# SCH_stm32f103c8t6_test1_2023-07-15.net
KiCad netlist of a schematic drawn in EasyEDA
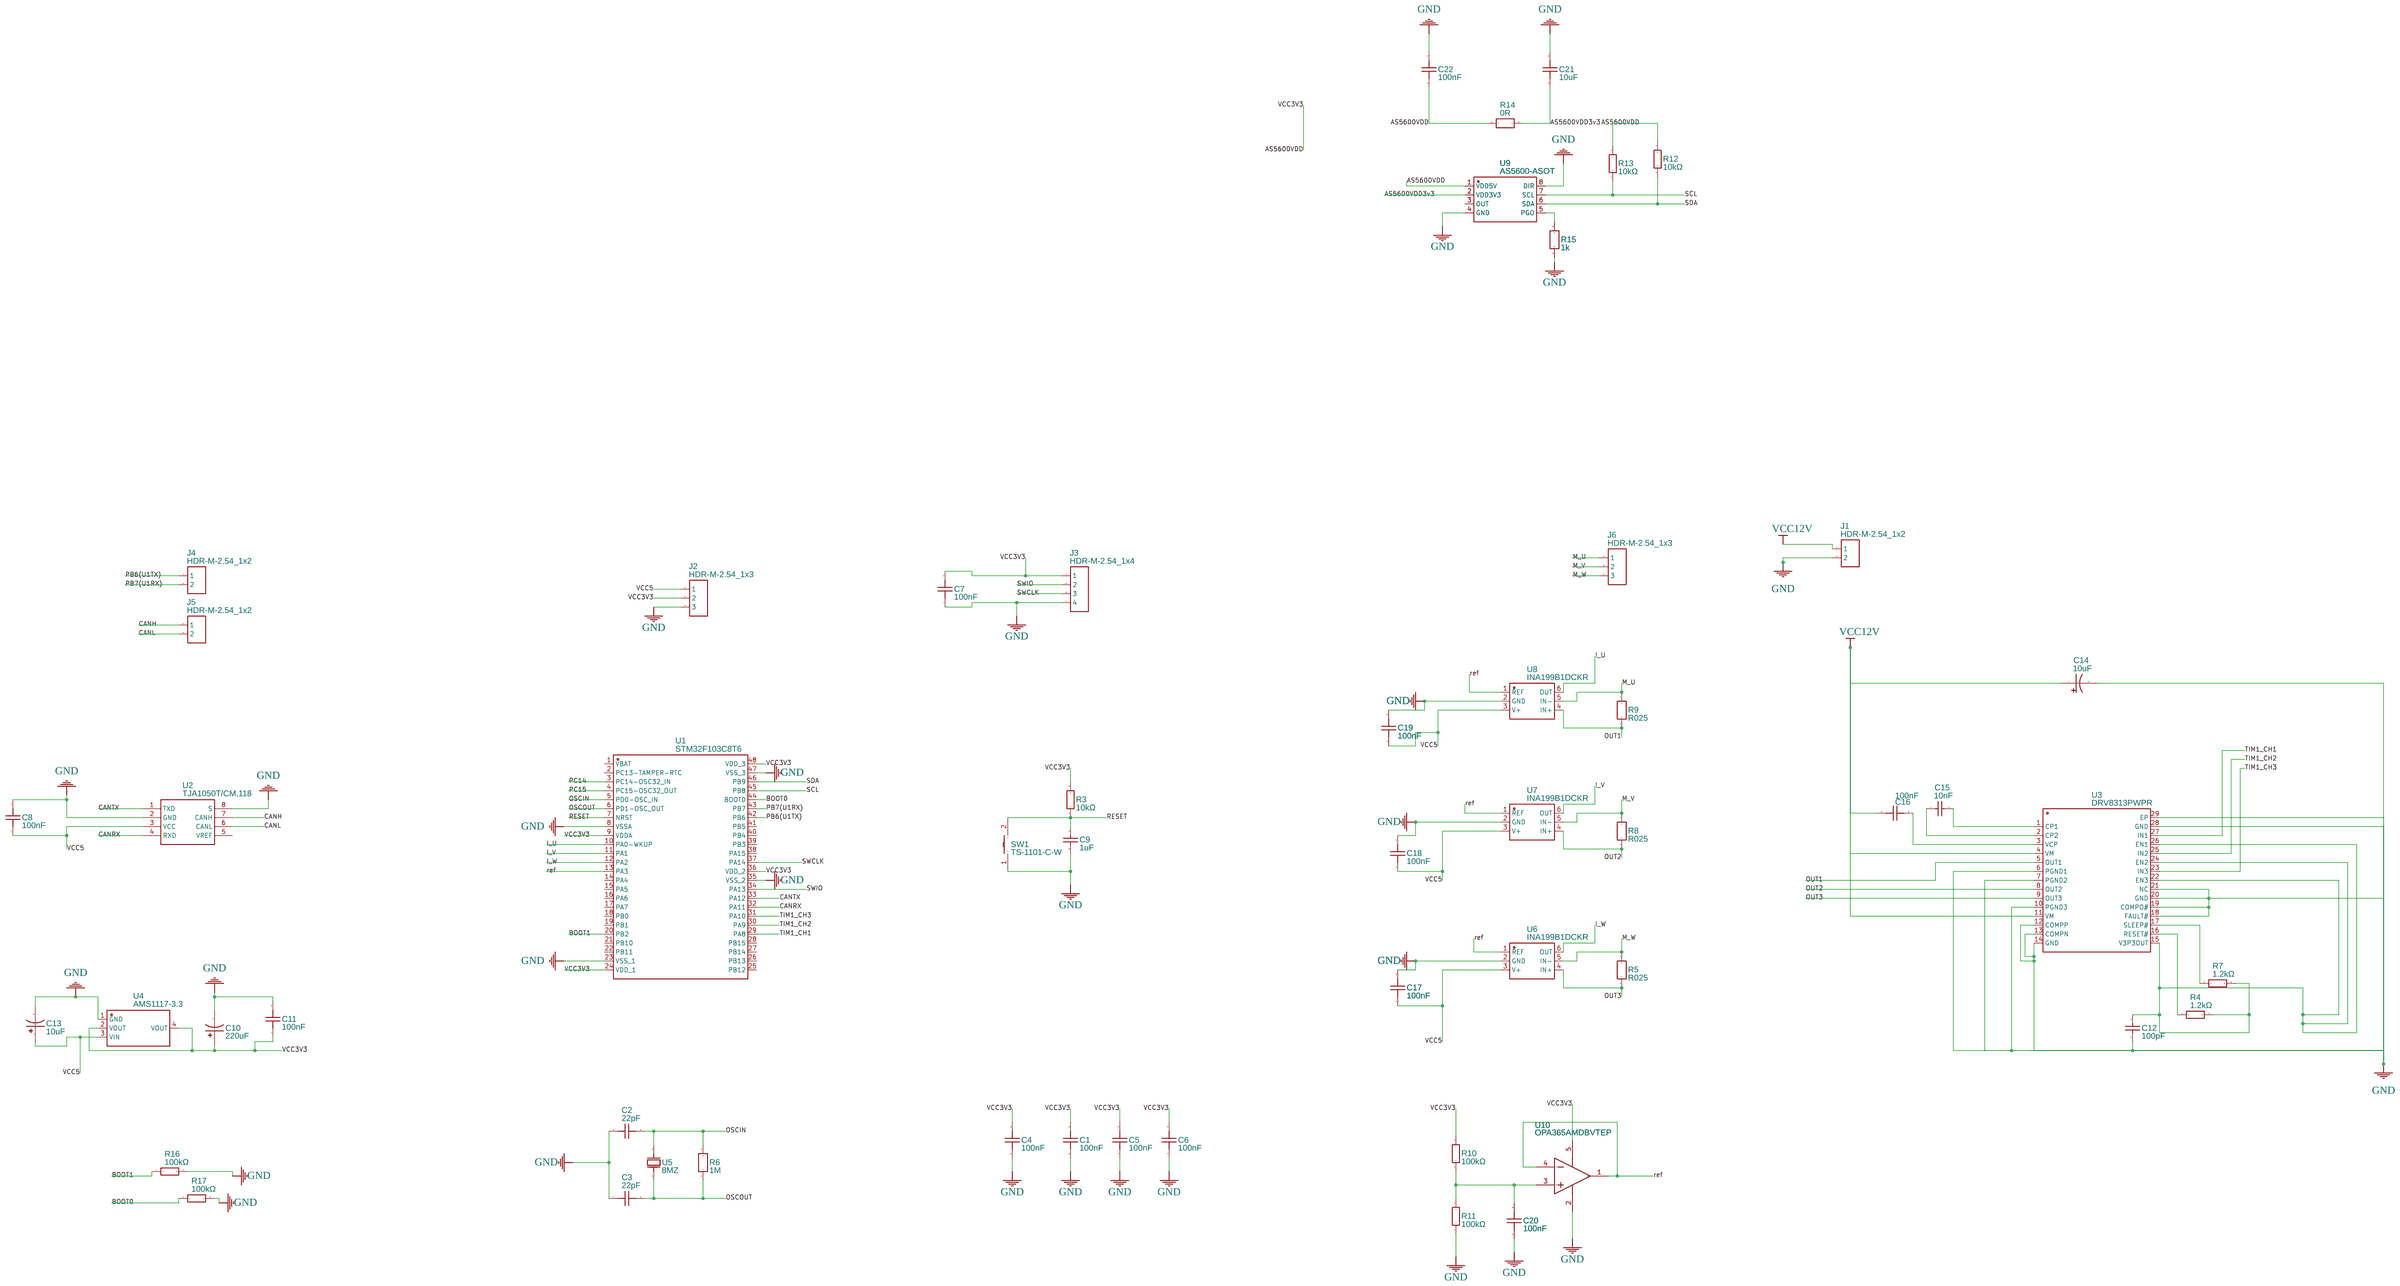
[diagram p0: schematic sheet]

(export (version "E")
  (design (tool "Eeschema 10.0.6"))
  (components
    (comp (ref "C1") (value "100nF") (libsource (lib "") (part "C_0603_US_1")))
    (comp (ref "C2") (value "22pF") (libsource (lib "") (part "C_0603_US")))
    (comp (ref "C3") (value "22pF") (libsource (lib "") (part "C_0603_US")))
    (comp (ref "C4") (value "100nF") (libsource (lib "") (part "C_0603_US_1")))
    (comp (ref "C5") (value "100nF") (libsource (lib "") (part "C_0603_US_1")))
    (comp (ref "C6") (value "100nF") (libsource (lib "") (part "C_0603_US_1")))
    (comp (ref "C7") (value "100nF") (libsource (lib "") (part "C_0603_US_1")))
    (comp (ref "C8") (value "100nF") (libsource (lib "") (part "C_0603_US_1")))
    (comp (ref "C9")
      (value "1uF")
      (fields
        (field (name "BOM_Manufacturer Part") "CGA3E1X7R1E105KT0Y0E")
        (field (name "BOM_Supplier Part") "C76708")
      )
      (libsource (lib "") (part "CGA3E1X7R1E105KT0Y0E"))
    )
    (comp (ref "C10") (value "220uF") (libsource (lib "") (part "C_Tan_SMD_C_US")))
    (comp (ref "C11") (value "100nF") (libsource (lib "") (part "C_0603_US_1")))
    (comp (ref "C12")
      (value "100pF")
      (fields
        (field (name "BOM_Manufacturer Part") "CGA3E2C0G2A101JT0Y0N")
        (field (name "BOM_Supplier Part") "C342908")
      )
      (libsource (lib "") (part "CGA3E2C0G2A101JT0Y0N"))
    )
    (comp (ref "C13") (value "10uF") (libsource (lib "") (part "C_Tan_SMD_A_US")))
    (comp (ref "C14")
      (value "10uF")
      (fields
        (field (name "BOM_Manufacturer Part") "NXA50VB10M5*11_LO")
        (field (name "BOM_Supplier Part") "C346966")
      )
      (libsource (lib "") (part "NXA50VB10M5*11_LO"))
    )
    (comp (ref "C15")
      (value "10nF")
      (fields
        (field (name "BOM_Manufacturer Part") "CGA3E2C0G1H103JT0Y0N")
        (field (name "BOM_Supplier Part") "C76710")
      )
      (libsource (lib "") (part "CGA3E2C0G1H103JT0Y0N"))
    )
    (comp (ref "C16")
      (value "100nF")
      (fields
        (field (name "BOM_Manufacturer Part") "0603B104K500")
        (field (name "BOM_Supplier Part") "C90807")
      )
      (libsource (lib "") (part "0603B104K500"))
    )
    (comp (ref "C17")
      (value "100nF")
      (fields
        (field (name "BOM_Manufacturer Part") "0603B104K500")
        (field (name "BOM_Supplier Part") "C90807")
      )
      (libsource (lib "") (part "0603B104K500_1"))
    )
    (comp (ref "C18")
      (value "100nF")
      (fields
        (field (name "BOM_Manufacturer Part") "0603B104K500")
        (field (name "BOM_Supplier Part") "C90807")
      )
      (libsource (lib "") (part "0603B104K500_1"))
    )
    (comp (ref "C19")
      (value "100nF")
      (fields
        (field (name "BOM_Manufacturer Part") "0603B104K500")
        (field (name "BOM_Supplier Part") "C90807")
      )
      (libsource (lib "") (part "0603B104K500_1"))
    )
    (comp (ref "C20") (value "100nF") (libsource (lib "") (part "C_0603_US_1")))
    (comp (ref "C21") (value "10uF") (libsource (lib "") (part "C_0603_US_1")))
    (comp (ref "C22") (value "100nF") (libsource (lib "") (part "C_0603_US_1")))
    (comp (ref "J1")
      (value "HDR-M-2.54_1x2")
      (fields (field (name "BOM_Supplier Part") "C124375"))
      (libsource (lib "") (part "HDR-M-2.54_1x2"))
    )
    (comp (ref "J2")
      (value "HDR-M-2.54_1x3")
      (fields (field (name "BOM_Supplier Part") "C180248"))
      (libsource (lib "") (part "HDR-M-2.54_1x3"))
    )
    (comp (ref "J3")
      (value "HDR-M-2.54_1x4")
      (fields (field (name "BOM_Supplier Part") "C124378"))
      (libsource (lib "") (part "HDR-M-2.54_1x4"))
    )
    (comp (ref "J4")
      (value "HDR-M-2.54_1x2")
      (fields (field (name "BOM_Supplier Part") "C124375"))
      (libsource (lib "") (part "HDR-M-2.54_1x2"))
    )
    (comp (ref "J5")
      (value "HDR-M-2.54_1x2")
      (fields (field (name "BOM_Supplier Part") "C124375"))
      (libsource (lib "") (part "HDR-M-2.54_1x2"))
    )
    (comp (ref "J6")
      (value "HDR-M-2.54_1x3")
      (fields (field (name "BOM_Supplier Part") "C180248"))
      (libsource (lib "") (part "HDR-M-2.54_1x3"))
    )
    (comp (ref "R3")
      (value "10kΩ")
      (fields
        (field (name "BOM_Manufacturer Part") "0603WAF1002T5E")
        (field (name "BOM_Supplier Part") "C25804")
      )
      (libsource (lib "") (part "0603WAF1002T5E"))
    )
    (comp (ref "R4")
      (value "1.2kΩ")
      (fields
        (field (name "BOM_Manufacturer Part") "RMC04021.2K1%N")
        (field (name "BOM_Supplier Part") "C325417")
      )
      (libsource (lib "") (part "RMC04021.2K1%N"))
    )
    (comp (ref "R5") (value "R025") (libsource (lib "") (part "R_2512_EU")))
    (comp (ref "R6") (value "1M") (libsource (lib "") (part "R_0603_EU")))
    (comp (ref "R7")
      (value "1.2kΩ")
      (fields
        (field (name "BOM_Manufacturer Part") "RMC04021.2K1%N")
        (field (name "BOM_Supplier Part") "C325417")
      )
      (libsource (lib "") (part "RMC04021.2K1%N"))
    )
    (comp (ref "R8") (value "R025") (libsource (lib "") (part "R_2512_EU")))
    (comp (ref "R9") (value "R025") (libsource (lib "") (part "R_2512_EU")))
    (comp (ref "R10")
      (value "100kΩ")
      (fields
        (field (name "BOM_Manufacturer Part") "AR03DTDX1003")
        (field (name "BOM_Supplier Part") "C319966")
      )
      (libsource (lib "") (part "AR03DTDX1003_1"))
    )
    (comp (ref "R11")
      (value "100kΩ")
      (fields
        (field (name "BOM_Manufacturer Part") "AR03DTDX1003")
        (field (name "BOM_Supplier Part") "C319966")
      )
      (libsource (lib "") (part "AR03DTDX1003_1"))
    )
    (comp (ref "R12")
      (value "10kΩ")
      (fields
        (field (name "BOM_Manufacturer Part") "0603WAF1002T5E")
        (field (name "BOM_Supplier Part") "C25804")
      )
      (libsource (lib "") (part "0603WAF1002T5E"))
    )
    (comp (ref "R13")
      (value "10kΩ")
      (fields
        (field (name "BOM_Manufacturer Part") "0603WAF1002T5E")
        (field (name "BOM_Supplier Part") "C25804")
      )
      (libsource (lib "") (part "0603WAF1002T5E"))
    )
    (comp (ref "R14") (value "0R") (libsource (lib "") (part "R_0603_EU_1")))
    (comp (ref "R15") (value "1k") (libsource (lib "") (part "R_0603_EU")))
    (comp (ref "R16")
      (value "100kΩ")
      (fields
        (field (name "BOM_Manufacturer Part") "AR03DTDX1003")
        (field (name "BOM_Supplier Part") "C319966")
      )
      (libsource (lib "") (part "AR03DTDX1003"))
    )
    (comp (ref "R17")
      (value "100kΩ")
      (fields
        (field (name "BOM_Manufacturer Part") "AR03DTDX1003")
        (field (name "BOM_Supplier Part") "C319966")
      )
      (libsource (lib "") (part "AR03DTDX1003"))
    )
    (comp (ref "SW1")
      (value "TS-1101-C-W")
      (fields (field (name "BOM_Supplier Part") "C318938"))
      (libsource (lib "") (part "TS-1101-C-W"))
    )
    (comp (ref "U1")
      (value "STM32F103C8T6")
      (fields (field (name "BOM_Supplier Part") "C8734"))
      (libsource (lib "") (part "STM32F103C8T6"))
    )
    (comp (ref "U2")
      (value "TJA1050T/CM,118")
      (fields (field (name "BOM_Supplier Part") "C6952"))
      (libsource (lib "") (part "TJA1050T/CM,118"))
    )
    (comp (ref "U3")
      (value "DRV8313PWPR")
      (fields (field (name "BOM_Supplier Part") "C92482"))
      (libsource (lib "") (part "DRV8313PWPR"))
    )
    (comp (ref "U4")
      (value "AMS1117-3.3")
      (fields (field (name "BOM_Supplier Part") "C6186"))
      (libsource (lib "") (part "AMS1117-3.3"))
    )
    (comp (ref "U5")
      (value "8MZ")
      (fields
        (field (name "BOM_Manufacturer Part") "S1C39321XWJAC")
        (field (name "BOM_Supplier Part") "C2764489")
      )
      (libsource (lib "") (part "S1C39321XWJAC"))
    )
    (comp (ref "U6")
      (value "INA199B1DCKR")
      (fields (field (name "BOM_Supplier Part") "C398920"))
      (libsource (lib "") (part "INA199B1DCKR"))
    )
    (comp (ref "U7")
      (value "INA199B1DCKR")
      (fields (field (name "BOM_Supplier Part") "C398920"))
      (libsource (lib "") (part "INA199B1DCKR"))
    )
    (comp (ref "U8")
      (value "INA199B1DCKR")
      (fields (field (name "BOM_Supplier Part") "C398920"))
      (libsource (lib "") (part "INA199B1DCKR"))
    )
    (comp (ref "U9")
      (value "AS5600-ASOT")
      (fields (field (name "BOM_Supplier Part") "C499458"))
      (libsource (lib "") (part "AS5600-ASOT"))
    )
    (comp (ref "U10")
      (value "OPA365AMDBVTEP")
      (fields (field (name "BOM_Supplier Part") "C2862994"))
      (libsource (lib "") (part "OPA365AMDBVTEP"))
    )
  )
  (nets
    (net (code "1") (name "/AS5600VDD") (class "Default")
      (node (ref "C1") (pin "2") (pinfunction "2_2") (pintype "unspecified"))
      (node (ref "C10") (pin "1") (pinfunction "1_1") (pintype "unspecified"))
      (node (ref "C11") (pin "1") (pinfunction "1_1") (pintype "unspecified"))
      (node (ref "C22") (pin "1") (pinfunction "1_1") (pintype "unspecified"))
      (node (ref "C4") (pin "2") (pinfunction "2_2") (pintype "unspecified"))
      (node (ref "C5") (pin "2") (pinfunction "2_2") (pintype "unspecified"))
      (node (ref "C6") (pin "2") (pinfunction "2_2") (pintype "unspecified"))
      (node (ref "C7") (pin "2") (pinfunction "2_2") (pintype "unspecified"))
      (node (ref "J2") (pin "2") (pinfunction "2_2") (pintype "input"))
      (node (ref "J3") (pin "1") (pinfunction "1_1") (pintype "unspecified"))
      (node (ref "R10") (pin "2") (pinfunction "2_2") (pintype "unspecified"))
      (node (ref "R12") (pin "2") (pinfunction "2_2") (pintype "input"))
      (node (ref "R13") (pin "2") (pinfunction "2_2") (pintype "input"))
      (node (ref "R14") (pin "1") (pinfunction "1_1") (pintype "unspecified"))
      (node (ref "R3") (pin "2") (pinfunction "2_2") (pintype "input"))
      (node (ref "U1") (pin "24") (pinfunction "VDD_1_24") (pintype "unspecified"))
      (node (ref "U1") (pin "36") (pinfunction "VDD_2_36") (pintype "unspecified"))
      (node (ref "U1") (pin "48") (pinfunction "VDD_3_48") (pintype "unspecified"))
      (node (ref "U1") (pin "9") (pinfunction "VDDA_9") (pintype "unspecified"))
      (node (ref "U10") (pin "5") (pinfunction "V+_5") (pintype "passive"))
      (node (ref "U4") (pin "2") (pinfunction "VOUT_2") (pintype "unspecified"))
      (node (ref "U4") (pin "4") (pinfunction "VOUT_4") (pintype "unspecified"))
      (node (ref "U9") (pin "1") (pinfunction "VDD5V_1") (pintype "unspecified"))
    )
    (net (code "2") (name "/AS5600VDD3v3") (class "Default")
      (node (ref "C21") (pin "1") (pinfunction "1_1") (pintype "unspecified"))
      (node (ref "R14") (pin "2") (pinfunction "2_2") (pintype "unspecified"))
      (node (ref "U9") (pin "2") (pinfunction "VDD3V3_2") (pintype "unspecified"))
    )
    (net (code "3") (name "/BOOT0") (class "Default")
      (node (ref "R17") (pin "1") (pinfunction "1_1") (pintype "unspecified"))
      (node (ref "U1") (pin "44") (pinfunction "BOOT0_44") (pintype "unspecified"))
    )
    (net (code "4") (name "/BOOT1") (class "Default")
      (node (ref "R16") (pin "1") (pinfunction "1_1") (pintype "unspecified"))
      (node (ref "U1") (pin "20") (pinfunction "PB2_20") (pintype "unspecified"))
    )
    (net (code "5") (name "/CANH") (class "Default")
      (node (ref "J5") (pin "1") (pinfunction "1_1") (pintype "unspecified"))
      (node (ref "U2") (pin "7") (pinfunction "CANH_7") (pintype "unspecified"))
    )
    (net (code "6") (name "/CANL") (class "Default")
      (node (ref "J5") (pin "2") (pinfunction "2_2") (pintype "unspecified"))
      (node (ref "U2") (pin "6") (pinfunction "CANL_6") (pintype "unspecified"))
    )
    (net (code "7") (name "/CANRX") (class "Default")
      (node (ref "U1") (pin "32") (pinfunction "PA11_32") (pintype "unspecified"))
      (node (ref "U2") (pin "4") (pinfunction "RXD_4") (pintype "unspecified"))
    )
    (net (code "8") (name "/CANTX") (class "Default")
      (node (ref "U1") (pin "33") (pinfunction "PA12_33") (pintype "unspecified"))
      (node (ref "U2") (pin "1") (pinfunction "TXD_1") (pintype "unspecified"))
    )
    (net (code "9") (name "/I_U") (class "Default")
      (node (ref "U1") (pin "10") (pinfunction "PA0-WKUP_10") (pintype "unspecified"))
      (node (ref "U8") (pin "6") (pinfunction "OUT_6") (pintype "unspecified"))
    )
    (net (code "10") (name "/I_V") (class "Default")
      (node (ref "U1") (pin "11") (pinfunction "PA1_11") (pintype "unspecified"))
      (node (ref "U7") (pin "6") (pinfunction "OUT_6") (pintype "unspecified"))
    )
    (net (code "11") (name "/I_W") (class "Default")
      (node (ref "U1") (pin "12") (pinfunction "PA2_12") (pintype "unspecified"))
      (node (ref "U6") (pin "6") (pinfunction "OUT_6") (pintype "unspecified"))
    )
    (net (code "12") (name "/M_U") (class "Default")
      (node (ref "J6") (pin "1") (pinfunction "1_1") (pintype "input"))
      (node (ref "R9") (pin "1") (pinfunction "1_1") (pintype "unspecified"))
      (node (ref "U8") (pin "5") (pinfunction "IN-_5") (pintype "unspecified"))
    )
    (net (code "13") (name "/M_V") (class "Default")
      (node (ref "J6") (pin "2") (pinfunction "2_2") (pintype "input"))
      (node (ref "R8") (pin "1") (pinfunction "1_1") (pintype "unspecified"))
      (node (ref "U7") (pin "5") (pinfunction "IN-_5") (pintype "unspecified"))
    )
    (net (code "14") (name "/M_W") (class "Default")
      (node (ref "J6") (pin "3") (pinfunction "3_3") (pintype "input"))
      (node (ref "R5") (pin "1") (pinfunction "1_1") (pintype "unspecified"))
      (node (ref "U6") (pin "5") (pinfunction "IN-_5") (pintype "unspecified"))
    )
    (net (code "15") (name "/OSCIN") (class "Default")
      (node (ref "C2") (pin "2") (pinfunction "2_2") (pintype "unspecified"))
      (node (ref "R6") (pin "2") (pinfunction "2_2") (pintype "unspecified"))
      (node (ref "U1") (pin "5") (pinfunction "PD0-OSC_IN_5") (pintype "unspecified"))
      (node (ref "U5") (pin "2") (pinfunction "OSC2_2") (pintype "input"))
    )
    (net (code "16") (name "/OSCOUT") (class "Default")
      (node (ref "C3") (pin "2") (pinfunction "2_2") (pintype "unspecified"))
      (node (ref "R6") (pin "1") (pinfunction "1_1") (pintype "unspecified"))
      (node (ref "U1") (pin "6") (pinfunction "PD1-OSC_OUT_6") (pintype "unspecified"))
      (node (ref "U5") (pin "1") (pinfunction "OSC1_1") (pintype "input"))
    )
    (net (code "17") (name "/OUT1") (class "Default")
      (node (ref "R9") (pin "2") (pinfunction "2_2") (pintype "unspecified"))
      (node (ref "U3") (pin "5") (pinfunction "OUT1_5") (pintype "unspecified"))
      (node (ref "U8") (pin "4") (pinfunction "IN+_4") (pintype "unspecified"))
    )
    (net (code "18") (name "/OUT2") (class "Default")
      (node (ref "R8") (pin "2") (pinfunction "2_2") (pintype "unspecified"))
      (node (ref "U3") (pin "8") (pinfunction "OUT2_8") (pintype "unspecified"))
      (node (ref "U7") (pin "4") (pinfunction "IN+_4") (pintype "unspecified"))
    )
    (net (code "19") (name "/OUT3") (class "Default")
      (node (ref "R5") (pin "2") (pinfunction "2_2") (pintype "unspecified"))
      (node (ref "U3") (pin "9") (pinfunction "OUT3_9") (pintype "unspecified"))
      (node (ref "U6") (pin "4") (pinfunction "IN+_4") (pintype "unspecified"))
    )
    (net (code "20") (name "/PB6(U1TX)") (class "Default")
      (node (ref "J4") (pin "1") (pinfunction "1_1") (pintype "unspecified"))
      (node (ref "U1") (pin "42") (pinfunction "PB6_42") (pintype "unspecified"))
    )
    (net (code "21") (name "/PB7(U1RX)") (class "Default")
      (node (ref "J4") (pin "2") (pinfunction "2_2") (pintype "unspecified"))
      (node (ref "U1") (pin "43") (pinfunction "PB7_43") (pintype "unspecified"))
    )
    (net (code "22") (name "/PC14") (class "Default")
      (node (ref "U1") (pin "3") (pinfunction "PC14-OSC32_IN_3") (pintype "unspecified"))
    )
    (net (code "23") (name "/PC15") (class "Default")
      (node (ref "U1") (pin "4") (pinfunction "PC15-OSC32_OUT_4") (pintype "unspecified"))
    )
    (net (code "24") (name "/RESET") (class "Default")
      (node (ref "C9") (pin "1") (pinfunction "1_1") (pintype "input"))
      (node (ref "R3") (pin "1") (pinfunction "1_1") (pintype "input"))
      (node (ref "SW1") (pin "2") (pinfunction "2_2") (pintype "unspecified"))
      (node (ref "U1") (pin "7") (pinfunction "NRST_7") (pintype "unspecified"))
    )
    (net (code "25") (name "/SCL") (class "Default")
      (node (ref "R13") (pin "1") (pinfunction "1_1") (pintype "input"))
      (node (ref "U1") (pin "45") (pinfunction "PB8_45") (pintype "unspecified"))
      (node (ref "U9") (pin "7") (pinfunction "SCL_7") (pintype "unspecified"))
    )
    (net (code "26") (name "/SDA") (class "Default")
      (node (ref "R12") (pin "1") (pinfunction "1_1") (pintype "input"))
      (node (ref "U1") (pin "46") (pinfunction "PB9_46") (pintype "unspecified"))
      (node (ref "U9") (pin "6") (pinfunction "SDA_6") (pintype "unspecified"))
    )
    (net (code "27") (name "/SWCLK") (class "Default")
      (node (ref "J3") (pin "3") (pinfunction "3_3") (pintype "unspecified"))
      (node (ref "U1") (pin "37") (pinfunction "PA14_37") (pintype "unspecified"))
    )
    (net (code "28") (name "/SWIO") (class "Default")
      (node (ref "J3") (pin "2") (pinfunction "2_2") (pintype "unspecified"))
      (node (ref "U1") (pin "34") (pinfunction "PA13_34") (pintype "unspecified"))
    )
    (net (code "29") (name "/TIM1_CH1") (class "Default")
      (node (ref "U1") (pin "29") (pinfunction "PA8_29") (pintype "unspecified"))
      (node (ref "U3") (pin "27") (pinfunction "IN1_27") (pintype "unspecified"))
    )
    (net (code "30") (name "/TIM1_CH2") (class "Default")
      (node (ref "U1") (pin "30") (pinfunction "PA9_30") (pintype "unspecified"))
      (node (ref "U3") (pin "25") (pinfunction "IN2_25") (pintype "unspecified"))
    )
    (net (code "31") (name "/TIM1_CH3") (class "Default")
      (node (ref "U1") (pin "31") (pinfunction "PA10_31") (pintype "unspecified"))
      (node (ref "U3") (pin "23") (pinfunction "IN3_23") (pintype "unspecified"))
    )
    (net (code "32") (name "/VCC5") (class "Default")
      (node (ref "C13") (pin "1") (pinfunction "1_1") (pintype "unspecified"))
      (node (ref "C17") (pin "1") (pinfunction "1_1") (pintype "unspecified"))
      (node (ref "C18") (pin "1") (pinfunction "1_1") (pintype "unspecified"))
      (node (ref "C19") (pin "1") (pinfunction "1_1") (pintype "unspecified"))
      (node (ref "C8") (pin "1") (pinfunction "1_1") (pintype "unspecified"))
      (node (ref "J2") (pin "1") (pinfunction "1_1") (pintype "input"))
      (node (ref "U2") (pin "3") (pinfunction "VCC_3") (pintype "unspecified"))
      (node (ref "U4") (pin "3") (pinfunction "VIN_3") (pintype "unspecified"))
      (node (ref "U6") (pin "3") (pinfunction "V+_3") (pintype "unspecified"))
      (node (ref "U7") (pin "3") (pinfunction "V+_3") (pintype "unspecified"))
      (node (ref "U8") (pin "3") (pinfunction "V+_3") (pintype "unspecified"))
    )
    (net (code "33") (name "/ref") (class "Default")
      (node (ref "U1") (pin "13") (pinfunction "PA3_13") (pintype "unspecified"))
      (node (ref "U10") (pin "1") (pinfunction "VOUT_1") (pintype "unspecified"))
      (node (ref "U10") (pin "4") (pinfunction "-IN_4") (pintype "unspecified"))
      (node (ref "U6") (pin "1") (pinfunction "REF_1") (pintype "unspecified"))
      (node (ref "U7") (pin "1") (pinfunction "REF_1") (pintype "unspecified"))
      (node (ref "U8") (pin "1") (pinfunction "REF_1") (pintype "unspecified"))
    )
    (net (code "34") (name "GND") (class "Default")
      (node (ref "C1") (pin "1") (pinfunction "1_1") (pintype "unspecified"))
      (node (ref "C10") (pin "2") (pinfunction "2_2") (pintype "unspecified"))
      (node (ref "C11") (pin "2") (pinfunction "2_2") (pintype "unspecified"))
      (node (ref "C12") (pin "2") (pinfunction "2_2") (pintype "input"))
      (node (ref "C13") (pin "2") (pinfunction "2_2") (pintype "unspecified"))
      (node (ref "C14") (pin "2") (pinfunction "2_2") (pintype "unspecified"))
      (node (ref "C17") (pin "2") (pinfunction "2_2") (pintype "unspecified"))
      (node (ref "C18") (pin "2") (pinfunction "2_2") (pintype "unspecified"))
      (node (ref "C19") (pin "2") (pinfunction "2_2") (pintype "unspecified"))
      (node (ref "C2") (pin "1") (pinfunction "1_1") (pintype "unspecified"))
      (node (ref "C20") (pin "1") (pinfunction "1_1") (pintype "unspecified"))
      (node (ref "C21") (pin "2") (pinfunction "2_2") (pintype "unspecified"))
      (node (ref "C22") (pin "2") (pinfunction "2_2") (pintype "unspecified"))
      (node (ref "C3") (pin "1") (pinfunction "1_1") (pintype "unspecified"))
      (node (ref "C4") (pin "1") (pinfunction "1_1") (pintype "unspecified"))
      (node (ref "C5") (pin "1") (pinfunction "1_1") (pintype "unspecified"))
      (node (ref "C6") (pin "1") (pinfunction "1_1") (pintype "unspecified"))
      (node (ref "C7") (pin "1") (pinfunction "1_1") (pintype "unspecified"))
      (node (ref "C8") (pin "2") (pinfunction "2_2") (pintype "unspecified"))
      (node (ref "C9") (pin "2") (pinfunction "2_2") (pintype "input"))
      (node (ref "J1") (pin "2") (pinfunction "2_2") (pintype "unspecified"))
      (node (ref "J2") (pin "3") (pinfunction "3_3") (pintype "input"))
      (node (ref "J3") (pin "4") (pinfunction "4_4") (pintype "unspecified"))
      (node (ref "R11") (pin "1") (pinfunction "1_1") (pintype "unspecified"))
      (node (ref "R15") (pin "1") (pinfunction "1_1") (pintype "unspecified"))
      (node (ref "R16") (pin "2") (pinfunction "2_2") (pintype "unspecified"))
      (node (ref "R17") (pin "2") (pinfunction "2_2") (pintype "unspecified"))
      (node (ref "SW1") (pin "1") (pinfunction "1_1") (pintype "unspecified"))
      (node (ref "U1") (pin "23") (pinfunction "VSS_1_23") (pintype "unspecified"))
      (node (ref "U1") (pin "35") (pinfunction "VSS_2_35") (pintype "unspecified"))
      (node (ref "U1") (pin "47") (pinfunction "VSS_3_47") (pintype "unspecified"))
      (node (ref "U1") (pin "8") (pinfunction "VSSA_8") (pintype "unspecified"))
      (node (ref "U10") (pin "2") (pinfunction "V-_2") (pintype "passive"))
      (node (ref "U2") (pin "2") (pinfunction "GND_2") (pintype "unspecified"))
      (node (ref "U2") (pin "8") (pinfunction "S_8") (pintype "unspecified"))
      (node (ref "U3") (pin "10") (pinfunction "PGND3_10") (pintype "unspecified"))
      (node (ref "U3") (pin "12") (pinfunction "COMPP_12") (pintype "unspecified"))
      (node (ref "U3") (pin "13") (pinfunction "COMPN_13") (pintype "unspecified"))
      (node (ref "U3") (pin "14") (pinfunction "GND_14") (pintype "unspecified"))
      (node (ref "U3") (pin "18") (pinfunction "FAULT#_18") (pintype "unspecified"))
      (node (ref "U3") (pin "19") (pinfunction "COMPO#_19") (pintype "unspecified"))
      (node (ref "U3") (pin "20") (pinfunction "GND_20") (pintype "unspecified"))
      (node (ref "U3") (pin "21") (pinfunction "NC_21") (pintype "unspecified"))
      (node (ref "U3") (pin "28") (pinfunction "GND_28") (pintype "unspecified"))
      (node (ref "U3") (pin "29") (pinfunction "EP_29") (pintype "unspecified"))
      (node (ref "U3") (pin "6") (pinfunction "PGND1_6") (pintype "unspecified"))
      (node (ref "U3") (pin "7") (pinfunction "PGND2_7") (pintype "unspecified"))
      (node (ref "U4") (pin "1") (pinfunction "GND_1") (pintype "unspecified"))
      (node (ref "U6") (pin "2") (pinfunction "GND_2") (pintype "unspecified"))
      (node (ref "U7") (pin "2") (pinfunction "GND_2") (pintype "unspecified"))
      (node (ref "U8") (pin "2") (pinfunction "GND_2") (pintype "unspecified"))
      (node (ref "U9") (pin "4") (pinfunction "GND_4") (pintype "unspecified"))
      (node (ref "U9") (pin "8") (pinfunction "DIR_8") (pintype "unspecified"))
    )
    (net (code "35") (name "Net-(U3-CP1)") (class "Default")
      (node (ref "C15") (pin "2") (pinfunction "2_2") (pintype "input"))
      (node (ref "U3") (pin "1") (pinfunction "CP1_1") (pintype "unspecified"))
    )
    (net (code "36") (name "Net-(U3-CP2)") (class "Default")
      (node (ref "C15") (pin "1") (pinfunction "1_1") (pintype "input"))
      (node (ref "U3") (pin "2") (pinfunction "CP2_2") (pintype "unspecified"))
    )
    (net (code "37") (name "Net-(U3-EN1)") (class "Default")
      (node (ref "C12") (pin "1") (pinfunction "1_1") (pintype "input"))
      (node (ref "R4") (pin "2") (pinfunction "2_2") (pintype "unspecified"))
      (node (ref "R7") (pin "2") (pinfunction "2_2") (pintype "unspecified"))
      (node (ref "U3") (pin "15") (pinfunction "V3P3OUT_15") (pintype "unspecified"))
      (node (ref "U3") (pin "22") (pinfunction "EN3_22") (pintype "unspecified"))
      (node (ref "U3") (pin "24") (pinfunction "EN2_24") (pintype "unspecified"))
      (node (ref "U3") (pin "26") (pinfunction "EN1_26") (pintype "unspecified"))
    )
    (net (code "38") (name "Net-(U3-RESET#)") (class "Default")
      (node (ref "R4") (pin "1") (pinfunction "1_1") (pintype "unspecified"))
      (node (ref "U3") (pin "16") (pinfunction "RESET#_16") (pintype "unspecified"))
    )
    (net (code "39") (name "Net-(U3-SLEEP#)") (class "Default")
      (node (ref "R7") (pin "1") (pinfunction "1_1") (pintype "unspecified"))
      (node (ref "U3") (pin "17") (pinfunction "SLEEP#_17") (pintype "unspecified"))
    )
    (net (code "40") (name "Net-(U3-VCP)") (class "Default")
      (node (ref "C16") (pin "2") (pinfunction "2_2") (pintype "unspecified"))
      (node (ref "U3") (pin "3") (pinfunction "VCP_3") (pintype "unspecified"))
    )
    (net (code "41") (name "Net-(U9-PGO)") (class "Default")
      (node (ref "R15") (pin "2") (pinfunction "2_2") (pintype "unspecified"))
      (node (ref "U9") (pin "5") (pinfunction "PGO_5") (pintype "unspecified"))
    )
    (net (code "42") (name "Net-(U10-+IN)") (class "Default")
      (node (ref "C20") (pin "2") (pinfunction "2_2") (pintype "unspecified"))
      (node (ref "R10") (pin "1") (pinfunction "1_1") (pintype "unspecified"))
      (node (ref "R11") (pin "2") (pinfunction "2_2") (pintype "unspecified"))
      (node (ref "U10") (pin "3") (pinfunction "+IN_3") (pintype "unspecified"))
    )
    (net (code "43") (name "VCC12V") (class "Default")
      (node (ref "C14") (pin "1") (pinfunction "1_1") (pintype "unspecified"))
      (node (ref "C16") (pin "1") (pinfunction "1_1") (pintype "unspecified"))
      (node (ref "J1") (pin "1") (pinfunction "1_1") (pintype "unspecified"))
      (node (ref "U3") (pin "11") (pinfunction "VM_11") (pintype "unspecified"))
      (node (ref "U3") (pin "4") (pinfunction "VM_4") (pintype "unspecified"))
    )
    (net (code "44") (name "unconnected-(U1-PA4-Pad14)") (class "Default")
      (node (ref "U1") (pin "14") (pinfunction "PA4_14") (pintype "unspecified"))
    )
    (net (code "45") (name "unconnected-(U1-PA5-Pad15)") (class "Default")
      (node (ref "U1") (pin "15") (pinfunction "PA5_15") (pintype "unspecified"))
    )
    (net (code "46") (name "unconnected-(U1-PA6-Pad16)") (class "Default")
      (node (ref "U1") (pin "16") (pinfunction "PA6_16") (pintype "unspecified"))
    )
    (net (code "47") (name "unconnected-(U1-PA7-Pad17)") (class "Default")
      (node (ref "U1") (pin "17") (pinfunction "PA7_17") (pintype "unspecified"))
    )
    (net (code "48") (name "unconnected-(U1-PA15-Pad38)") (class "Default")
      (node (ref "U1") (pin "38") (pinfunction "PA15_38") (pintype "unspecified"))
    )
    (net (code "49") (name "unconnected-(U1-PB0-Pad18)") (class "Default")
      (node (ref "U1") (pin "18") (pinfunction "PB0_18") (pintype "unspecified"))
    )
    (net (code "50") (name "unconnected-(U1-PB1-Pad19)") (class "Default")
      (node (ref "U1") (pin "19") (pinfunction "PB1_19") (pintype "unspecified"))
    )
    (net (code "51") (name "unconnected-(U1-PB3-Pad39)") (class "Default")
      (node (ref "U1") (pin "39") (pinfunction "PB3_39") (pintype "unspecified"))
    )
    (net (code "52") (name "unconnected-(U1-PB4-Pad40)") (class "Default")
      (node (ref "U1") (pin "40") (pinfunction "PB4_40") (pintype "unspecified"))
    )
    (net (code "53") (name "unconnected-(U1-PB5-Pad41)") (class "Default")
      (node (ref "U1") (pin "41") (pinfunction "PB5_41") (pintype "unspecified"))
    )
    (net (code "54") (name "unconnected-(U1-PB10-Pad21)") (class "Default")
      (node (ref "U1") (pin "21") (pinfunction "PB10_21") (pintype "unspecified"))
    )
    (net (code "55") (name "unconnected-(U1-PB11-Pad22)") (class "Default")
      (node (ref "U1") (pin "22") (pinfunction "PB11_22") (pintype "unspecified"))
    )
    (net (code "56") (name "unconnected-(U1-PB12-Pad25)") (class "Default")
      (node (ref "U1") (pin "25") (pinfunction "PB12_25") (pintype "unspecified"))
    )
    (net (code "57") (name "unconnected-(U1-PB13-Pad26)") (class "Default")
      (node (ref "U1") (pin "26") (pinfunction "PB13_26") (pintype "unspecified"))
    )
    (net (code "58") (name "unconnected-(U1-PB14-Pad27)") (class "Default")
      (node (ref "U1") (pin "27") (pinfunction "PB14_27") (pintype "unspecified"))
    )
    (net (code "59") (name "unconnected-(U1-PB15-Pad28)") (class "Default")
      (node (ref "U1") (pin "28") (pinfunction "PB15_28") (pintype "unspecified"))
    )
    (net (code "60") (name "unconnected-(U1-PC13-TAMPER-RTC-Pad2)") (class "Default")
      (node (ref "U1") (pin "2") (pinfunction "PC13-TAMPER-RTC_2") (pintype "unspecified"))
    )
    (net (code "61") (name "unconnected-(U1-VBAT-Pad1)") (class "Default")
      (node (ref "U1") (pin "1") (pinfunction "VBAT_1") (pintype "unspecified"))
    )
    (net (code "62") (name "unconnected-(U2-VREF-Pad5)") (class "Default")
      (node (ref "U2") (pin "5") (pinfunction "VREF_5") (pintype "unspecified"))
    )
    (net (code "63") (name "unconnected-(U9-OUT-Pad3)") (class "Default")
      (node (ref "U9") (pin "3") (pinfunction "OUT_3") (pintype "unspecified"))
    )
  )
)
